# USB_board.net
KiCad netlist of a schematic drawn in EAGLE
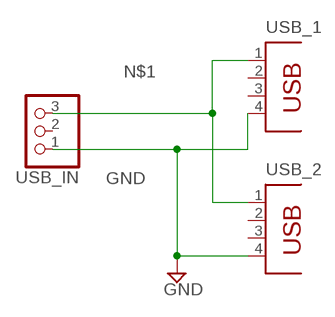
[diagram p0: schematic, sheet 1]

(export (version "E")
  (design (tool "Eeschema 10.0.6"))
  (components
    (comp (ref "USB_1")
      (value "PN87520")
      (footprint "eagle-import:PN87520")
      (libsource (lib "eagle-import") (part "PN87520"))
    )
    (comp (ref "USB_2")
      (value "PN87520")
      (footprint "eagle-import:PN87520")
      (libsource (lib "eagle-import") (part "PN87520"))
    )
    (comp (ref "USB_IN")
      (value "PINHD-1X3")
      (footprint "eagle-import:1X03")
      (libsource (lib "eagle-import") (part "PINHD-1X3"))
    )
  )
  (nets
    (net (code "1") (name "/N$1") (class "Default")
      (node (ref "USB_1") (pin "1") (pinfunction "1_1") (pintype "passive"))
      (node (ref "USB_2") (pin "1") (pinfunction "1_1") (pintype "passive"))
      (node (ref "USB_IN") (pin "3") (pinfunction "3_3") (pintype "passive"))
    )
    (net (code "2") (name "GND") (class "Default")
      (node (ref "USB_1") (pin "4") (pinfunction "4_4") (pintype "passive"))
      (node (ref "USB_2") (pin "4") (pinfunction "4_4") (pintype "passive"))
      (node (ref "USB_IN") (pin "1") (pinfunction "1_1") (pintype "passive"))
    )
    (net (code "3") (name "unconnected-(USB_1-Pad2)") (class "Default")
      (node (ref "USB_1") (pin "2") (pinfunction "2_2") (pintype "passive"))
    )
    (net (code "4") (name "unconnected-(USB_1-Pad3)") (class "Default")
      (node (ref "USB_1") (pin "3") (pinfunction "3_3") (pintype "passive"))
    )
    (net (code "5") (name "unconnected-(USB_2-Pad2)") (class "Default")
      (node (ref "USB_2") (pin "2") (pinfunction "2_2") (pintype "passive"))
    )
    (net (code "6") (name "unconnected-(USB_2-Pad3)") (class "Default")
      (node (ref "USB_2") (pin "3") (pinfunction "3_3") (pintype "passive"))
    )
    (net (code "7") (name "unconnected-(USB_IN-Pad2)") (class "Default")
      (node (ref "USB_IN") (pin "2") (pinfunction "2_2") (pintype "passive"))
    )
  )
)
